# blimpy-1_0-B.net
KiCad netlist of a schematic drawn in EAGLE
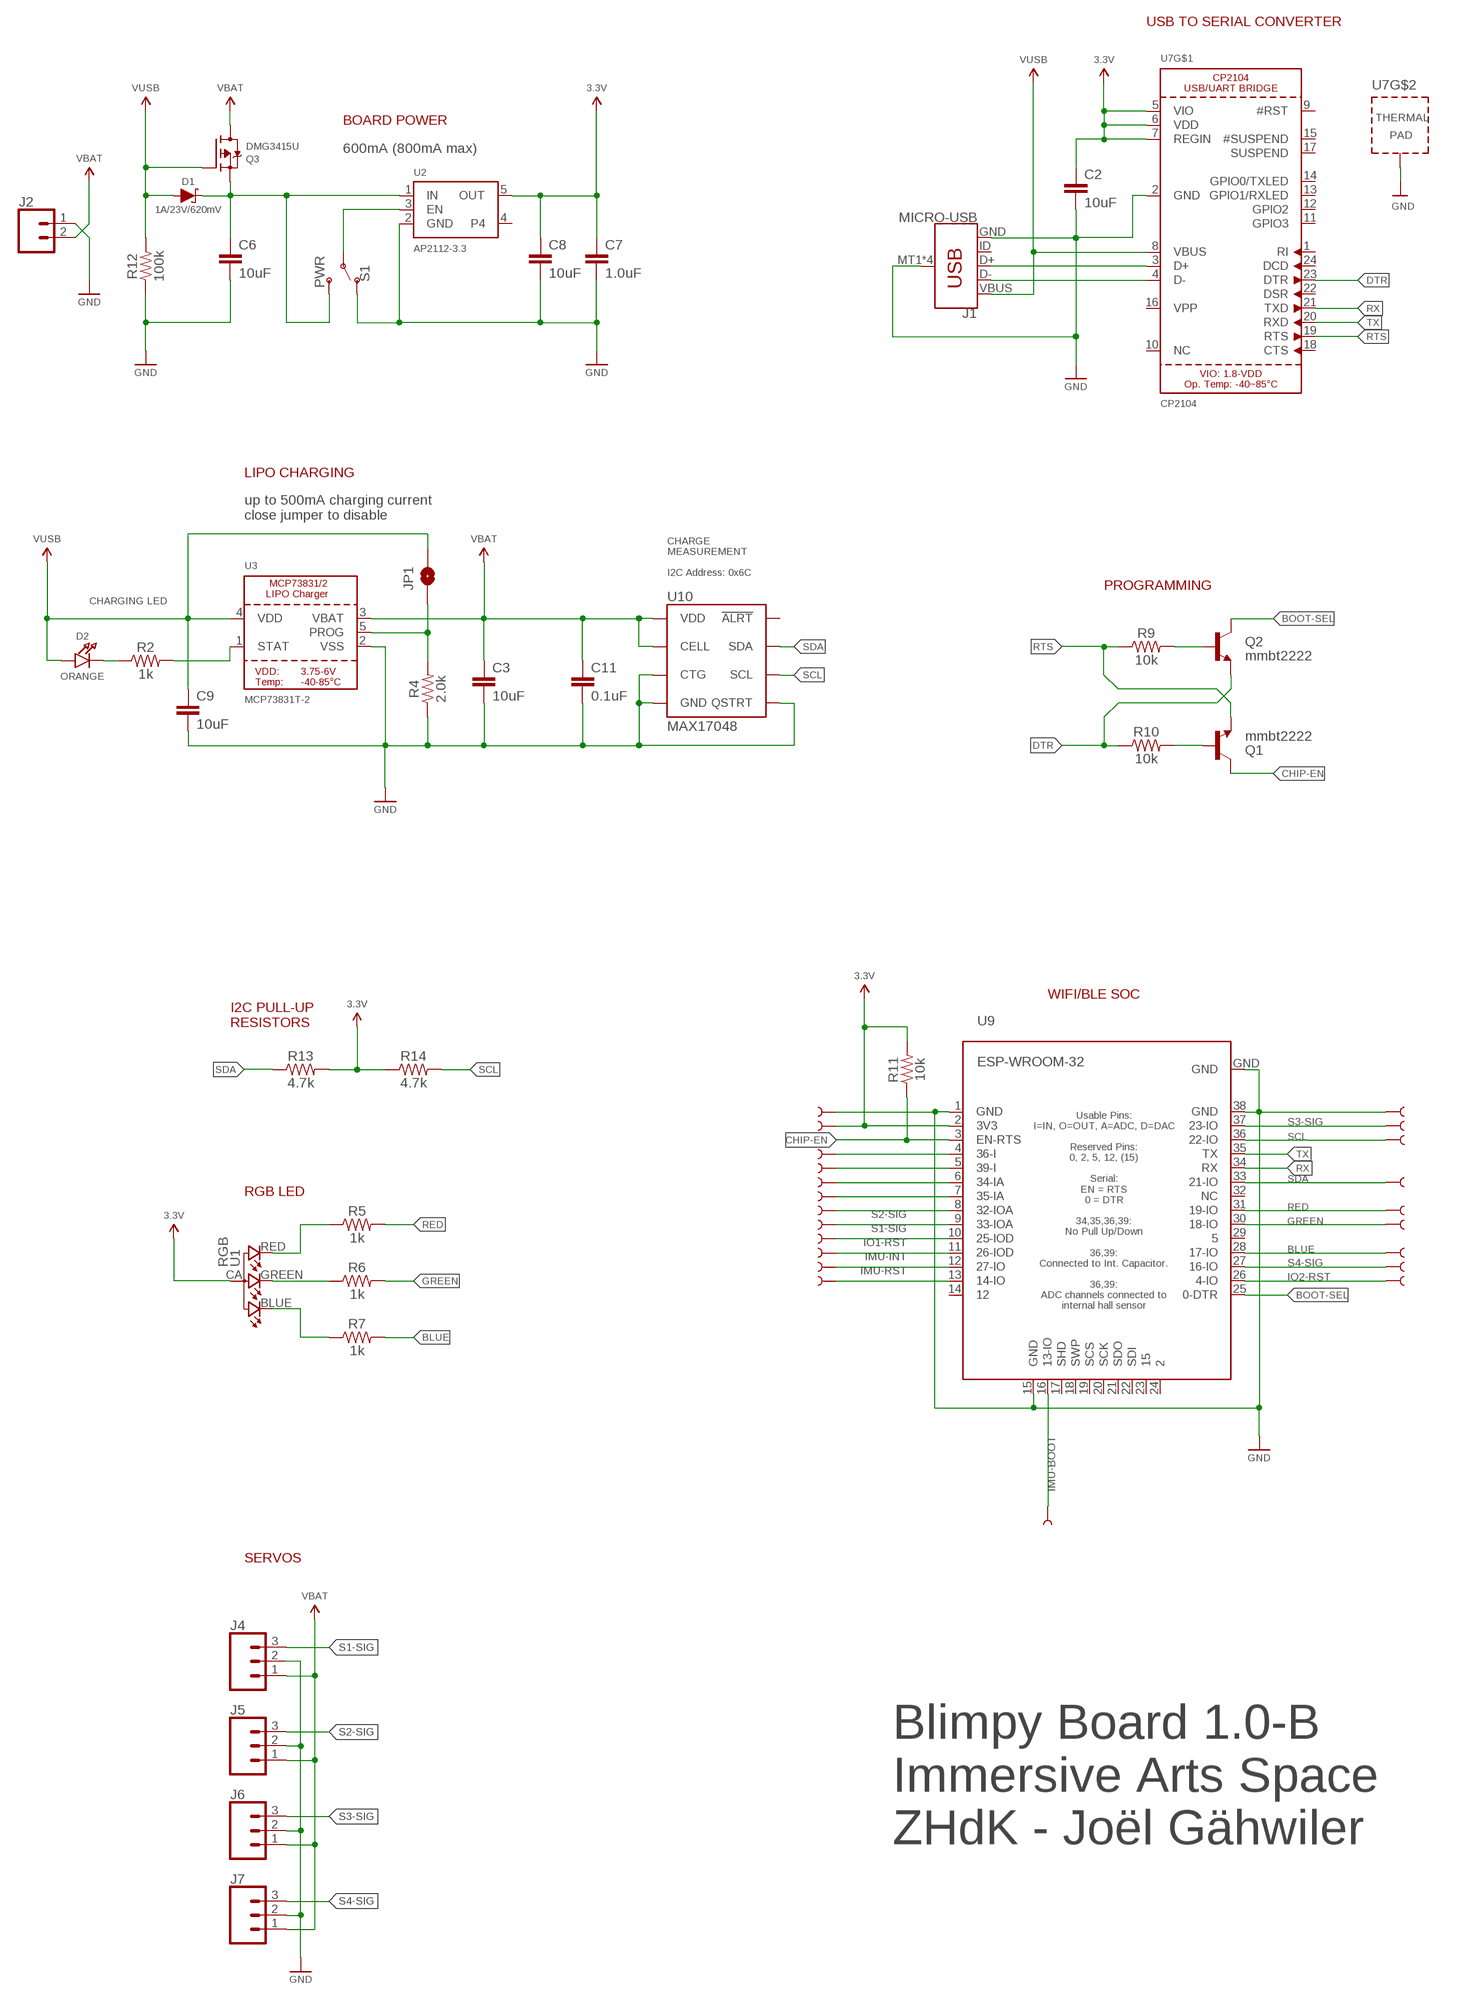
[diagram p0: schematic, sheet 1, part 1 of 2]
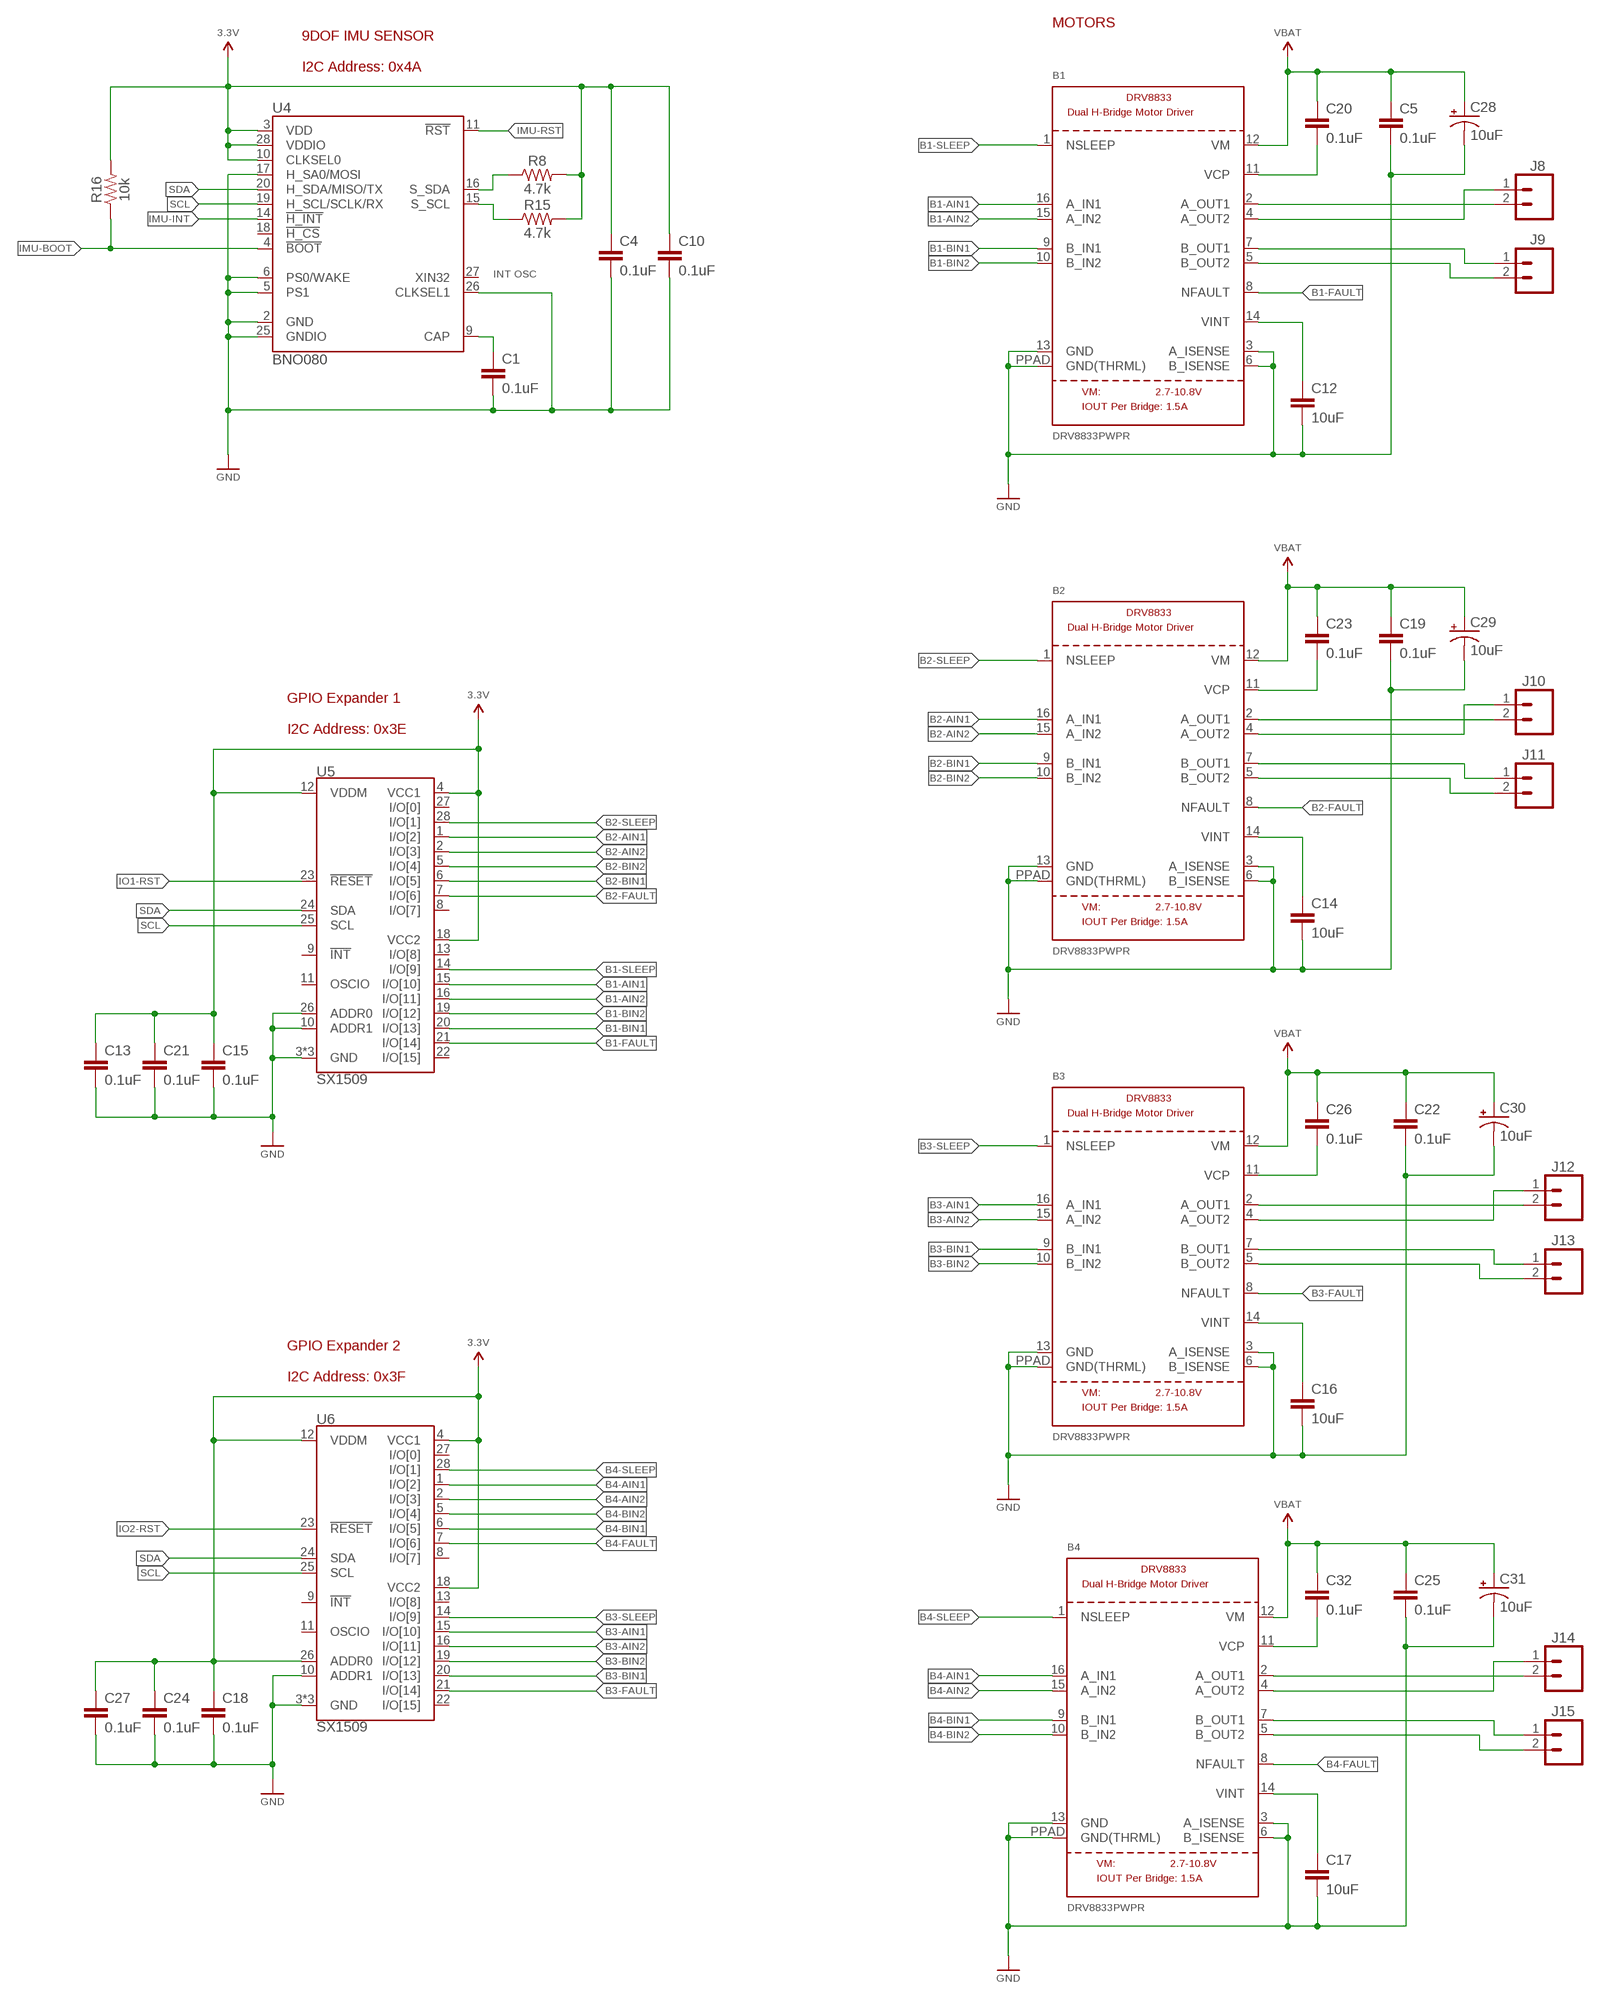
[diagram p1: schematic, sheet 1, part 2 of 2]

(export (version "E")
  (design (tool "Eeschema 10.0.6"))
  (components
    (comp (ref "B1")
      (value "DRV8833PWPR")
      (footprint "eagle-import:HTSSOP16")
      (libsource (lib "eagle-import") (part "DRV8833"))
    )
    (comp (ref "B2")
      (value "DRV8833PWPR")
      (footprint "eagle-import:HTSSOP16")
      (libsource (lib "eagle-import") (part "DRV8833"))
    )
    (comp (ref "B3")
      (value "DRV8833PWPR")
      (footprint "eagle-import:HTSSOP16")
      (libsource (lib "eagle-import") (part "DRV8833"))
    )
    (comp (ref "B4")
      (value "DRV8833PWPR")
      (footprint "eagle-import:HTSSOP16")
      (libsource (lib "eagle-import") (part "DRV8833"))
    )
    (comp (ref "C1")
      (value "0.1uF")
      (footprint "eagle-import:0603")
      (libsource (lib "eagle-import") (part "0.1UF-0603-25V-5%"))
    )
    (comp (ref "C2")
      (value "10uF")
      (footprint "eagle-import:0603")
      (libsource (lib "eagle-import") (part "10UF-0603-6.3V-20%"))
    )
    (comp (ref "C3")
      (value "10uF")
      (footprint "eagle-import:0603")
      (libsource (lib "eagle-import") (part "10UF-0603-6.3V-20%"))
    )
    (comp (ref "C4")
      (value "0.1uF")
      (footprint "eagle-import:0603")
      (libsource (lib "eagle-import") (part "0.1UF-0603-25V-5%"))
    )
    (comp (ref "C5")
      (value "0.1uF")
      (footprint "eagle-import:0603")
      (libsource (lib "eagle-import") (part "0.1UF-0603-25V-5%"))
    )
    (comp (ref "C6")
      (value "10uF")
      (footprint "eagle-import:0603")
      (libsource (lib "eagle-import") (part "10UF-0603-6.3V-20%"))
    )
    (comp (ref "C7")
      (value "1.0uF")
      (footprint "eagle-import:0603")
      (libsource (lib "eagle-import") (part "1.0UF-0603-16V-10%"))
    )
    (comp (ref "C8")
      (value "10uF")
      (footprint "eagle-import:0603")
      (libsource (lib "eagle-import") (part "10UF-0603-6.3V-20%"))
    )
    (comp (ref "C9")
      (value "10uF")
      (footprint "eagle-import:0603")
      (libsource (lib "eagle-import") (part "10UF-0603-6.3V-20%"))
    )
    (comp (ref "C10")
      (value "0.1uF")
      (footprint "eagle-import:0603")
      (libsource (lib "eagle-import") (part "0.1UF-0603-25V-5%"))
    )
    (comp (ref "C11")
      (value "0.1uF")
      (footprint "eagle-import:0603")
      (libsource (lib "eagle-import") (part "SparkFun-Capacitors_510_0.1UF-0603-25V-5%"))
    )
    (comp (ref "C12")
      (value "10uF")
      (footprint "eagle-import:0603")
      (libsource (lib "eagle-import") (part "10UF-0603-6.3V-20%"))
    )
    (comp (ref "C13")
      (value "0.1uF")
      (footprint "eagle-import:0603")
      (libsource (lib "eagle-import") (part "0.1UF-0603-25V-5%"))
    )
    (comp (ref "C14")
      (value "10uF")
      (footprint "eagle-import:0603")
      (libsource (lib "eagle-import") (part "10UF-0603-6.3V-20%"))
    )
    (comp (ref "C15")
      (value "0.1uF")
      (footprint "eagle-import:0603")
      (libsource (lib "eagle-import") (part "SparkFun-Capacitors_510_0.1UF-0603-25V-5%"))
    )
    (comp (ref "C16")
      (value "10uF")
      (footprint "eagle-import:0603")
      (libsource (lib "eagle-import") (part "10UF-0603-6.3V-20%"))
    )
    (comp (ref "C17")
      (value "10uF")
      (footprint "eagle-import:0603")
      (libsource (lib "eagle-import") (part "10UF-0603-6.3V-20%"))
    )
    (comp (ref "C18")
      (value "0.1uF")
      (footprint "eagle-import:0603")
      (libsource (lib "eagle-import") (part "SparkFun-Capacitors_510_0.1UF-0603-25V-5%"))
    )
    (comp (ref "C19")
      (value "0.1uF")
      (footprint "eagle-import:0603")
      (libsource (lib "eagle-import") (part "0.1UF-0603-25V-5%"))
    )
    (comp (ref "C20")
      (value "0.1uF")
      (footprint "eagle-import:0603")
      (libsource (lib "eagle-import") (part "0.1UF-0603-25V-5%"))
    )
    (comp (ref "C21")
      (value "0.1uF")
      (footprint "eagle-import:0603")
      (libsource (lib "eagle-import") (part "0.1UF-0603-25V-5%"))
    )
    (comp (ref "C22")
      (value "0.1uF")
      (footprint "eagle-import:0603")
      (libsource (lib "eagle-import") (part "0.1UF-0603-25V-5%"))
    )
    (comp (ref "C23")
      (value "0.1uF")
      (footprint "eagle-import:0603")
      (libsource (lib "eagle-import") (part "0.1UF-0603-25V-5%"))
    )
    (comp (ref "C24")
      (value "0.1uF")
      (footprint "eagle-import:0603")
      (libsource (lib "eagle-import") (part "0.1UF-0603-25V-5%"))
    )
    (comp (ref "C25")
      (value "0.1uF")
      (footprint "eagle-import:0603")
      (libsource (lib "eagle-import") (part "0.1UF-0603-25V-5%"))
    )
    (comp (ref "C26")
      (value "0.1uF")
      (footprint "eagle-import:0603")
      (libsource (lib "eagle-import") (part "0.1UF-0603-25V-5%"))
    )
    (comp (ref "C27")
      (value "0.1uF")
      (footprint "eagle-import:0603")
      (libsource (lib "eagle-import") (part "0.1UF-0603-25V-5%"))
    )
    (comp (ref "C28")
      (value "10uF")
      (footprint "eagle-import:EIA3216")
      (libsource (lib "eagle-import") (part "10UF-POLAR-EIA3216-16V-10%(TANT)"))
    )
    (comp (ref "C29")
      (value "10uF")
      (footprint "eagle-import:EIA3216")
      (libsource (lib "eagle-import") (part "10UF-POLAR-EIA3216-16V-10%(TANT)"))
    )
    (comp (ref "C30")
      (value "10uF")
      (footprint "eagle-import:EIA3216")
      (libsource (lib "eagle-import") (part "10UF-POLAR-EIA3216-16V-10%(TANT)"))
    )
    (comp (ref "C31")
      (value "10uF")
      (footprint "eagle-import:EIA3216")
      (libsource (lib "eagle-import") (part "10UF-POLAR-EIA3216-16V-10%(TANT)"))
    )
    (comp (ref "C32")
      (value "0.1uF")
      (footprint "eagle-import:0603")
      (libsource (lib "eagle-import") (part "0.1UF-0603-25V-5%"))
    )
    (comp (ref "D1")
      (value "1A/23V/620mV")
      (footprint "eagle-import:SOD-323")
      (libsource (lib "eagle-import") (part "DIODE-SCHOTTKY-BAT20J"))
    )
    (comp (ref "D2")
      (value "ORANGE")
      (footprint "eagle-import:CHIPLED_0805_NOOUTLINE")
      (libsource (lib "eagle-import") (part "LED0805_NOOUTLINE"))
    )
    (comp (ref "J1")
      (value "MICRO-USB")
      (footprint "eagle-import:USB-MICROB")
      (libsource (lib "eagle-import") (part "USB_MICRO-B_SMT"))
    )
    (comp (ref "J2")
      (value "CONN_02-JST-2MM-SMT")
      (footprint "eagle-import:JST-2-SMD")
      (libsource (lib "eagle-import") (part "CONN_02-JST-2MM-SMT"))
    )
    (comp (ref "J4")
      (value "3-PIN SMD")
      (footprint "eagle-import:JST-3-SMD")
      (libsource (lib "eagle-import") (part "CONN_03JST-SMD"))
    )
    (comp (ref "J5")
      (value "3-PIN SMD")
      (footprint "eagle-import:JST-3-SMD")
      (libsource (lib "eagle-import") (part "CONN_03JST-SMD"))
    )
    (comp (ref "J6")
      (value "3-PIN SMD")
      (footprint "eagle-import:JST-3-SMD")
      (libsource (lib "eagle-import") (part "CONN_03JST-SMD"))
    )
    (comp (ref "J7")
      (value "3-PIN SMD")
      (footprint "eagle-import:JST-3-SMD")
      (libsource (lib "eagle-import") (part "CONN_03JST-SMD"))
    )
    (comp (ref "J8")
      (value "CONN_02-JST-2MM-SMT")
      (footprint "eagle-import:JST-2-SMD")
      (libsource (lib "eagle-import") (part "CONN_02-JST-2MM-SMT"))
    )
    (comp (ref "J9")
      (value "CONN_02-JST-2MM-SMT")
      (footprint "eagle-import:JST-2-SMD")
      (libsource (lib "eagle-import") (part "CONN_02-JST-2MM-SMT"))
    )
    (comp (ref "J10")
      (value "CONN_02-JST-2MM-SMT")
      (footprint "eagle-import:JST-2-SMD")
      (libsource (lib "eagle-import") (part "CONN_02-JST-2MM-SMT"))
    )
    (comp (ref "J11")
      (value "CONN_02-JST-2MM-SMT")
      (footprint "eagle-import:JST-2-SMD")
      (libsource (lib "eagle-import") (part "CONN_02-JST-2MM-SMT"))
    )
    (comp (ref "J12")
      (value "CONN_02-JST-2MM-SMT")
      (footprint "eagle-import:JST-2-SMD")
      (libsource (lib "eagle-import") (part "CONN_02-JST-2MM-SMT"))
    )
    (comp (ref "J13")
      (value "CONN_02-JST-2MM-SMT")
      (footprint "eagle-import:JST-2-SMD")
      (libsource (lib "eagle-import") (part "CONN_02-JST-2MM-SMT"))
    )
    (comp (ref "J14")
      (value "CONN_02-JST-2MM-SMT")
      (footprint "eagle-import:JST-2-SMD")
      (libsource (lib "eagle-import") (part "CONN_02-JST-2MM-SMT"))
    )
    (comp (ref "J15")
      (value "CONN_02-JST-2MM-SMT")
      (footprint "eagle-import:JST-2-SMD")
      (libsource (lib "eagle-import") (part "CONN_02-JST-2MM-SMT"))
    )
    (comp (ref "JP1")
      (value "JUMPER-SMT_2_NO_SILK")
      (footprint "eagle-import:SMT-JUMPER_2_NO_SILK")
      (libsource (lib "eagle-import") (part "JUMPER-SMT_2_NO_SILK"))
    )
    (comp (ref "Q1")
      (value "mmbt2222")
      (footprint "eagle-import:SOT23-3")
      (libsource (lib "eagle-import") (part "TRANSISTOR_NPNSOT23-3"))
    )
    (comp (ref "Q2")
      (value "mmbt2222")
      (footprint "eagle-import:SOT23-3")
      (libsource (lib "eagle-import") (part "TRANSISTOR_NPNSOT23-3"))
    )
    (comp (ref "Q3")
      (value "DMG3415U")
      (footprint "eagle-import:SOT23-R")
      (libsource (lib "eagle-import") (part "MOSFET-P"))
    )
    (comp (ref "R2")
      (value "1k")
      (footprint "eagle-import:0603")
      (libsource (lib "eagle-import") (part "1KOHM-0603-1/10W-1%"))
    )
    (comp (ref "R4")
      (value "2.0k")
      (footprint "eagle-import:0603")
      (libsource (lib "eagle-import") (part "2.0KOHM-0603-1/10W-5%"))
    )
    (comp (ref "R5")
      (value "1k")
      (footprint "eagle-import:0603")
      (libsource (lib "eagle-import") (part "1KOHM-0603-1/10W-1%"))
    )
    (comp (ref "R6")
      (value "1k")
      (footprint "eagle-import:0603")
      (libsource (lib "eagle-import") (part "1KOHM-0603-1/10W-1%"))
    )
    (comp (ref "R7")
      (value "1k")
      (footprint "eagle-import:0603")
      (libsource (lib "eagle-import") (part "1KOHM-0603-1/10W-1%"))
    )
    (comp (ref "R8")
      (value "4.7k")
      (footprint "eagle-import:0603")
      (libsource (lib "eagle-import") (part "4.7KOHM-0603-1/10W-1%"))
    )
    (comp (ref "R9")
      (value "10k")
      (footprint "eagle-import:0603")
      (libsource (lib "eagle-import") (part "10KOHM-0603-1/10W-1%"))
    )
    (comp (ref "R10")
      (value "10k")
      (footprint "eagle-import:0603")
      (libsource (lib "eagle-import") (part "10KOHM-0603-1/10W-1%"))
    )
    (comp (ref "R11")
      (value "10k")
      (footprint "eagle-import:0603")
      (libsource (lib "eagle-import") (part "10KOHM-0603-1/10W-1%"))
    )
    (comp (ref "R12")
      (value "100k")
      (footprint "eagle-import:0603")
      (libsource (lib "eagle-import") (part "100KOHM-0603-1/10W-1%"))
    )
    (comp (ref "R13")
      (value "4.7k")
      (footprint "eagle-import:0603")
      (libsource (lib "eagle-import") (part "4.7KOHM-0603-1/10W-1%"))
    )
    (comp (ref "R14")
      (value "4.7k")
      (footprint "eagle-import:0603")
      (libsource (lib "eagle-import") (part "4.7KOHM-0603-1/10W-1%"))
    )
    (comp (ref "R15")
      (value "4.7k")
      (footprint "eagle-import:0603")
      (libsource (lib "eagle-import") (part "4.7KOHM-0603-1/10W-1%"))
    )
    (comp (ref "R16")
      (value "10k")
      (footprint "eagle-import:0603")
      (libsource (lib "eagle-import") (part "10KOHM-0603-1/10W-1%"))
    )
    (comp (ref "S1")
      (value "PWR")
      (footprint "eagle-import:SWITCH_SPST_SMD_A")
      (libsource (lib "eagle-import") (part "SWITCH-SPDT-SMD-RIGHT-ANGLE"))
    )
    (comp (ref "TP1")
      (value "TEST-POINT3")
      (footprint "eagle-import:PAD.03X.03")
      (libsource (lib "eagle-import") (part "TEST-POINT3"))
    )
    (comp (ref "TP2")
      (value "TEST-POINT3")
      (footprint "eagle-import:PAD.03X.03")
      (libsource (lib "eagle-import") (part "TEST-POINT3"))
    )
    (comp (ref "TP3")
      (value "TEST-POINT3")
      (footprint "eagle-import:PAD.03X.03")
      (libsource (lib "eagle-import") (part "TEST-POINT3"))
    )
    (comp (ref "TP4")
      (value "TEST-POINT3")
      (footprint "eagle-import:PAD.03X.03")
      (libsource (lib "eagle-import") (part "TEST-POINT3"))
    )
    (comp (ref "TP5")
      (value "TEST-POINT3")
      (footprint "eagle-import:PAD.03X.03")
      (libsource (lib "eagle-import") (part "TEST-POINT3"))
    )
    (comp (ref "TP6")
      (value "TEST-POINT3")
      (footprint "eagle-import:PAD.03X.03")
      (libsource (lib "eagle-import") (part "TEST-POINT3"))
    )
    (comp (ref "TP7")
      (value "TEST-POINT3")
      (footprint "eagle-import:PAD.03X.03")
      (libsource (lib "eagle-import") (part "TEST-POINT3"))
    )
    (comp (ref "TP8")
      (value "TEST-POINT3")
      (footprint "eagle-import:PAD.03X.03")
      (libsource (lib "eagle-import") (part "TEST-POINT3"))
    )
    (comp (ref "TP9")
      (value "TEST-POINT3")
      (footprint "eagle-import:PAD.03X.03")
      (libsource (lib "eagle-import") (part "TEST-POINT3"))
    )
    (comp (ref "TP10")
      (value "TEST-POINT3")
      (footprint "eagle-import:PAD.03X.03")
      (libsource (lib "eagle-import") (part "TEST-POINT3"))
    )
    (comp (ref "TP11")
      (value "TEST-POINT3")
      (footprint "eagle-import:PAD.03X.03")
      (libsource (lib "eagle-import") (part "TEST-POINT3"))
    )
    (comp (ref "TP12")
      (value "TEST-POINT3")
      (footprint "eagle-import:PAD.03X.03")
      (libsource (lib "eagle-import") (part "TEST-POINT3"))
    )
    (comp (ref "TP13")
      (value "TEST-POINT3")
      (footprint "eagle-import:PAD.03X.03")
      (libsource (lib "eagle-import") (part "TEST-POINT3"))
    )
    (comp (ref "TP14")
      (value "TEST-POINT3")
      (footprint "eagle-import:PAD.03X.03")
      (libsource (lib "eagle-import") (part "TEST-POINT3"))
    )
    (comp (ref "TP15")
      (value "TEST-POINT3")
      (footprint "eagle-import:PAD.03X.03")
      (libsource (lib "eagle-import") (part "TEST-POINT3"))
    )
    (comp (ref "TP16")
      (value "TEST-POINT3")
      (footprint "eagle-import:PAD.03X.03")
      (libsource (lib "eagle-import") (part "TEST-POINT3"))
    )
    (comp (ref "TP17")
      (value "TEST-POINT3")
      (footprint "eagle-import:PAD.03X.03")
      (libsource (lib "eagle-import") (part "TEST-POINT3"))
    )
    (comp (ref "TP18")
      (value "TEST-POINT3")
      (footprint "eagle-import:PAD.03X.03")
      (libsource (lib "eagle-import") (part "TEST-POINT3"))
    )
    (comp (ref "TP19")
      (value "TEST-POINT3")
      (footprint "eagle-import:PAD.03X.03")
      (libsource (lib "eagle-import") (part "TEST-POINT3"))
    )
    (comp (ref "TP20")
      (value "TEST-POINT3")
      (footprint "eagle-import:PAD.03X.03")
      (libsource (lib "eagle-import") (part "TEST-POINT3"))
    )
    (comp (ref "TP21")
      (value "TEST-POINT3")
      (footprint "eagle-import:PAD.03X.03")
      (libsource (lib "eagle-import") (part "TEST-POINT3"))
    )
    (comp (ref "TP22")
      (value "TEST-POINT3")
      (footprint "eagle-import:PAD.03X.03")
      (libsource (lib "eagle-import") (part "TEST-POINT3"))
    )
    (comp (ref "U1")
      (value "RGB")
      (footprint "eagle-import:PLCC4-2MM-RGB")
      (libsource (lib "eagle-import") (part "RGB-LED-CLMVB-FKARGB"))
    )
    (comp (ref "U2")
      (value "AP2112-3.3")
      (footprint "eagle-import:SOT23-5")
      (libsource (lib "eagle-import") (part "VREG_SOT23-5"))
    )
    (comp (ref "U3")
      (value "MCP73831T-2")
      (footprint "eagle-import:SOT23-5")
      (libsource (lib "eagle-import") (part "MCP73831/2"))
    )
    (comp (ref "U4")
      (value "BNO080")
      (footprint "eagle-import:LGA-28")
      (libsource (lib "eagle-import") (part "BNO080"))
    )
    (comp (ref "U5")
      (value "SX1509")
      (footprint "eagle-import:QFN-28")
      (libsource (lib "eagle-import") (part "SX1509"))
    )
    (comp (ref "U6")
      (value "SX1509")
      (footprint "eagle-import:QFN-28")
      (libsource (lib "eagle-import") (part "SX1509"))
    )
    (comp (ref "U7")
      (value "CP2104")
      (footprint "eagle-import:QFN24_4MM_SMSC")
      (libsource (lib "eagle-import") (part "CP2104"))
    )
    (comp (ref "U9")
      (value "ESP-WROOM-32")
      (footprint "eagle-import:ESP-WROOM-32")
      (libsource (lib "eagle-import") (part "ESP-WROOM-32"))
    )
    (comp (ref "U10")
      (value "MAX17048")
      (footprint "eagle-import:DFN-8")
      (libsource (lib "eagle-import") (part "MAX17048DFN8"))
    )
  )
  (nets
    (net (code "1") (name "3.3V") (class "Default")
      (node (ref "C10") (pin "1") (pinfunction "1_1") (pintype "passive"))
      (node (ref "C13") (pin "1") (pinfunction "1_1") (pintype "passive"))
      (node (ref "C15") (pin "1") (pinfunction "1_1") (pintype "passive"))
      (node (ref "C18") (pin "1") (pinfunction "1_1") (pintype "passive"))
      (node (ref "C2") (pin "1") (pinfunction "1_1") (pintype "passive"))
      (node (ref "C21") (pin "1") (pinfunction "1_1") (pintype "passive"))
      (node (ref "C24") (pin "1") (pinfunction "1_1") (pintype "passive"))
      (node (ref "C27") (pin "1") (pinfunction "1_1") (pintype "passive"))
      (node (ref "C4") (pin "1") (pinfunction "1_1") (pintype "passive"))
      (node (ref "C7") (pin "1") (pinfunction "1_1") (pintype "passive"))
      (node (ref "C8") (pin "1") (pinfunction "1_1") (pintype "passive"))
      (node (ref "R11") (pin "2") (pinfunction "2_2") (pintype "passive"))
      (node (ref "R13") (pin "2") (pinfunction "2_2") (pintype "passive"))
      (node (ref "R14") (pin "1") (pinfunction "1_1") (pintype "passive"))
      (node (ref "R15") (pin "2") (pinfunction "2_2") (pintype "passive"))
      (node (ref "R16") (pin "2") (pinfunction "2_2") (pintype "passive"))
      (node (ref "R8") (pin "2") (pinfunction "2_2") (pintype "passive"))
      (node (ref "TP11") (pin "P$1") (pinfunction "1_P$1") (pintype "bidirectional"))
      (node (ref "U1") (pin "CA") (pinfunction "1_CA") (pintype "passive"))
      (node (ref "U2") (pin "5") (pinfunction "OUT_5") (pintype "power_in"))
      (node (ref "U4") (pin "10") (pinfunction "CLKSEL0_10") (pintype "bidirectional"))
      (node (ref "U4") (pin "28") (pinfunction "VDDIO_28") (pintype "bidirectional"))
      (node (ref "U4") (pin "3") (pinfunction "VDD_3") (pintype "bidirectional"))
      (node (ref "U5") (pin "12") (pinfunction "VDDM_12") (pintype "bidirectional"))
      (node (ref "U5") (pin "18") (pinfunction "VCC2_18") (pintype "bidirectional"))
      (node (ref "U5") (pin "4") (pinfunction "VCC1_4") (pintype "bidirectional"))
      (node (ref "U6") (pin "12") (pinfunction "VDDM_12") (pintype "bidirectional"))
      (node (ref "U6") (pin "18") (pinfunction "VCC2_18") (pintype "bidirectional"))
      (node (ref "U6") (pin "26") (pinfunction "ADDR0_26") (pintype "bidirectional"))
      (node (ref "U6") (pin "4") (pinfunction "VCC1_4") (pintype "bidirectional"))
      (node (ref "U7") (pin "5") (pinfunction "VIO_5") (pintype "power_in"))
      (node (ref "U7") (pin "6") (pinfunction "VDD_6") (pintype "power_in"))
      (node (ref "U7") (pin "7") (pinfunction "REGIN_7") (pintype "power_in"))
      (node (ref "U9") (pin "2") (pinfunction "3V3_2") (pintype "bidirectional"))
    )
    (net (code "2") (name "B1-AIN1") (class "Default")
      (node (ref "B1") (pin "16") (pinfunction "A_IN1_16") (pintype "input"))
      (node (ref "U5") (pin "15") (pinfunction "I/O[10]_15") (pintype "bidirectional"))
    )
    (net (code "3") (name "B1-AIN2") (class "Default")
      (node (ref "B1") (pin "15") (pinfunction "A_IN2_15") (pintype "input"))
      (node (ref "U5") (pin "16") (pinfunction "I/O[11]_16") (pintype "bidirectional"))
    )
    (net (code "4") (name "B1-BIN1") (class "Default")
      (node (ref "B1") (pin "9") (pinfunction "B_IN1_9") (pintype "input"))
      (node (ref "U5") (pin "20") (pinfunction "I/O[13]_20") (pintype "bidirectional"))
    )
    (net (code "5") (name "B1-BIN2") (class "Default")
      (node (ref "B1") (pin "10") (pinfunction "B_IN2_10") (pintype "input"))
      (node (ref "U5") (pin "19") (pinfunction "I/O[12]_19") (pintype "bidirectional"))
    )
    (net (code "6") (name "B1-FAULT") (class "Default")
      (node (ref "B1") (pin "8") (pinfunction "NFAULT_8") (pintype "bidirectional"))
      (node (ref "U5") (pin "21") (pinfunction "I/O[14]_21") (pintype "bidirectional"))
    )
    (net (code "7") (name "B1-SLEEP") (class "Default")
      (node (ref "B1") (pin "1") (pinfunction "NSLEEP_1") (pintype "input"))
      (node (ref "U5") (pin "14") (pinfunction "I/O[9]_14") (pintype "bidirectional"))
    )
    (net (code "8") (name "B2-AIN1") (class "Default")
      (node (ref "B2") (pin "16") (pinfunction "A_IN1_16") (pintype "input"))
      (node (ref "U5") (pin "1") (pinfunction "I/O[2]_1") (pintype "bidirectional"))
    )
    (net (code "9") (name "B2-AIN2") (class "Default")
      (node (ref "B2") (pin "15") (pinfunction "A_IN2_15") (pintype "input"))
      (node (ref "U5") (pin "2") (pinfunction "I/O[3]_2") (pintype "bidirectional"))
    )
    (net (code "10") (name "B2-BIN1") (class "Default")
      (node (ref "B2") (pin "9") (pinfunction "B_IN1_9") (pintype "input"))
      (node (ref "U5") (pin "6") (pinfunction "I/O[5]_6") (pintype "bidirectional"))
    )
    (net (code "11") (name "B2-BIN2") (class "Default")
      (node (ref "B2") (pin "10") (pinfunction "B_IN2_10") (pintype "input"))
      (node (ref "U5") (pin "5") (pinfunction "I/O[4]_5") (pintype "bidirectional"))
    )
    (net (code "12") (name "B2-FAULT") (class "Default")
      (node (ref "B2") (pin "8") (pinfunction "NFAULT_8") (pintype "bidirectional"))
      (node (ref "U5") (pin "7") (pinfunction "I/O[6]_7") (pintype "bidirectional"))
    )
    (net (code "13") (name "B2-SLEEP") (class "Default")
      (node (ref "B2") (pin "1") (pinfunction "NSLEEP_1") (pintype "input"))
      (node (ref "U5") (pin "28") (pinfunction "I/O[1]_28") (pintype "bidirectional"))
    )
    (net (code "14") (name "B3-AIN1") (class "Default")
      (node (ref "B3") (pin "16") (pinfunction "A_IN1_16") (pintype "input"))
      (node (ref "U6") (pin "15") (pinfunction "I/O[10]_15") (pintype "bidirectional"))
    )
    (net (code "15") (name "B3-AIN2") (class "Default")
      (node (ref "B3") (pin "15") (pinfunction "A_IN2_15") (pintype "input"))
      (node (ref "U6") (pin "16") (pinfunction "I/O[11]_16") (pintype "bidirectional"))
    )
    (net (code "16") (name "B3-BIN1") (class "Default")
      (node (ref "B3") (pin "9") (pinfunction "B_IN1_9") (pintype "input"))
      (node (ref "U6") (pin "20") (pinfunction "I/O[13]_20") (pintype "bidirectional"))
    )
    (net (code "17") (name "B3-BIN2") (class "Default")
      (node (ref "B3") (pin "10") (pinfunction "B_IN2_10") (pintype "input"))
      (node (ref "U6") (pin "19") (pinfunction "I/O[12]_19") (pintype "bidirectional"))
    )
    (net (code "18") (name "B3-FAULT") (class "Default")
      (node (ref "B3") (pin "8") (pinfunction "NFAULT_8") (pintype "bidirectional"))
      (node (ref "U6") (pin "21") (pinfunction "I/O[14]_21") (pintype "bidirectional"))
    )
    (net (code "19") (name "B3-SLEEP") (class "Default")
      (node (ref "B3") (pin "1") (pinfunction "NSLEEP_1") (pintype "input"))
      (node (ref "U6") (pin "14") (pinfunction "I/O[9]_14") (pintype "bidirectional"))
    )
    (net (code "20") (name "B4-AIN1") (class "Default")
      (node (ref "B4") (pin "16") (pinfunction "A_IN1_16") (pintype "input"))
      (node (ref "U6") (pin "1") (pinfunction "I/O[2]_1") (pintype "bidirectional"))
    )
    (net (code "21") (name "B4-AIN2") (class "Default")
      (node (ref "B4") (pin "15") (pinfunction "A_IN2_15") (pintype "input"))
      (node (ref "U6") (pin "2") (pinfunction "I/O[3]_2") (pintype "bidirectional"))
    )
    (net (code "22") (name "B4-BIN1") (class "Default")
      (node (ref "B4") (pin "9") (pinfunction "B_IN1_9") (pintype "input"))
      (node (ref "U6") (pin "6") (pinfunction "I/O[5]_6") (pintype "bidirectional"))
    )
    (net (code "23") (name "B4-BIN2") (class "Default")
      (node (ref "B4") (pin "10") (pinfunction "B_IN2_10") (pintype "input"))
      (node (ref "U6") (pin "5") (pinfunction "I/O[4]_5") (pintype "bidirectional"))
    )
    (net (code "24") (name "B4-FAULT") (class "Default")
      (node (ref "B4") (pin "8") (pinfunction "NFAULT_8") (pintype "bidirectional"))
      (node (ref "U6") (pin "7") (pinfunction "I/O[6]_7") (pintype "bidirectional"))
    )
    (net (code "25") (name "B4-SLEEP") (class "Default")
      (node (ref "B4") (pin "1") (pinfunction "NSLEEP_1") (pintype "input"))
      (node (ref "U6") (pin "28") (pinfunction "I/O[1]_28") (pintype "bidirectional"))
    )
    (net (code "26") (name "BLUE") (class "Default")
      (node (ref "R7") (pin "2") (pinfunction "2_2") (pintype "passive"))
      (node (ref "TP22") (pin "P$1") (pinfunction "1_P$1") (pintype "bidirectional"))
      (node (ref "U9") (pin "28") (pinfunction "17-IO_28") (pintype "bidirectional"))
    )
    (net (code "27") (name "BOOT-SEL") (class "Default")
      (node (ref "Q2") (pin "3") (pinfunction "C_3") (pintype "passive"))
      (node (ref "U9") (pin "25") (pinfunction "0-DTR_25") (pintype "bidirectional"))
    )
    (net (code "28") (name "CHIP-EN") (class "Default")
      (node (ref "Q1") (pin "3") (pinfunction "C_3") (pintype "passive"))
      (node (ref "R11") (pin "1") (pinfunction "1_1") (pintype "passive"))
      (node (ref "U9") (pin "3") (pinfunction "EN-RTS_3") (pintype "bidirectional"))
    )
    (net (code "29") (name "DTR") (class "Default")
      (node (ref "Q2") (pin "2") (pinfunction "E_2") (pintype "passive"))
      (node (ref "R10") (pin "1") (pinfunction "1_1") (pintype "passive"))
      (node (ref "U7") (pin "23") (pinfunction "DTR_23") (pintype "output"))
    )
    (net (code "30") (name "GND") (class "Default")
      (node (ref "B1") (pin "13") (pinfunction "GND_13") (pintype "power_in"))
      (node (ref "B1") (pin "3") (pinfunction "A_ISENSE_3") (pintype "bidirectional"))
      (node (ref "B1") (pin "6") (pinfunction "B_ISENSE_6") (pintype "bidirectional"))
      (node (ref "B1") (pin "PPAD") (pinfunction "GND(THRML)_PPAD") (pintype "power_in"))
      (node (ref "B2") (pin "13") (pinfunction "GND_13") (pintype "power_in"))
      (node (ref "B2") (pin "3") (pinfunction "A_ISENSE_3") (pintype "bidirectional"))
      (node (ref "B2") (pin "6") (pinfunction "B_ISENSE_6") (pintype "bidirectional"))
      (node (ref "B2") (pin "PPAD") (pinfunction "GND(THRML)_PPAD") (pintype "power_in"))
      (node (ref "B3") (pin "13") (pinfunction "GND_13") (pintype "power_in"))
      (node (ref "B3") (pin "3") (pinfunction "A_ISENSE_3") (pintype "bidirectional"))
      (node (ref "B3") (pin "6") (pinfunction "B_ISENSE_6") (pintype "bidirectional"))
      (node (ref "B3") (pin "PPAD") (pinfunction "GND(THRML)_PPAD") (pintype "power_in"))
      (node (ref "B4") (pin "13") (pinfunction "GND_13") (pintype "power_in"))
      (node (ref "B4") (pin "3") (pinfunction "A_ISENSE_3") (pintype "bidirectional"))
      (node (ref "B4") (pin "6") (pinfunction "B_ISENSE_6") (pintype "bidirectional"))
      (node (ref "B4") (pin "PPAD") (pinfunction "GND(THRML)_PPAD") (pintype "power_in"))
      (node (ref "C1") (pin "2") (pinfunction "2_2") (pintype "passive"))
      (node (ref "C10") (pin "2") (pinfunction "2_2") (pintype "passive"))
      (node (ref "C11") (pin "2") (pinfunction "2_2") (pintype "passive"))
      (node (ref "C12") (pin "2") (pinfunction "2_2") (pintype "passive"))
      (node (ref "C13") (pin "2") (pinfunction "2_2") (pintype "passive"))
      (node (ref "C14") (pin "2") (pinfunction "2_2") (pintype "passive"))
      (node (ref "C15") (pin "2") (pinfunction "2_2") (pintype "passive"))
      (node (ref "C16") (pin "2") (pinfunction "2_2") (pintype "passive"))
      (node (ref "C17") (pin "2") (pinfunction "2_2") (pintype "passive"))
      (node (ref "C18") (pin "2") (pinfunction "2_2") (pintype "passive"))
      (node (ref "C19") (pin "2") (pinfunction "2_2") (pintype "passive"))
      (node (ref "C2") (pin "2") (pinfunction "2_2") (pintype "passive"))
      (node (ref "C21") (pin "2") (pinfunction "2_2") (pintype "passive"))
      (node (ref "C22") (pin "2") (pinfunction "2_2") (pintype "passive"))
      (node (ref "C24") (pin "2") (pinfunction "2_2") (pintype "passive"))
      (node (ref "C25") (pin "2") (pinfunction "2_2") (pintype "passive"))
      (node (ref "C27") (pin "2") (pinfunction "2_2") (pintype "passive"))
      (node (ref "C28") (pin "-") (pinfunction "-_-") (pintype "passive"))
      (node (ref "C29") (pin "-") (pinfunction "-_-") (pintype "passive"))
      (node (ref "C3") (pin "2") (pinfunction "2_2") (pintype "passive"))
      (node (ref "C30") (pin "-") (pinfunction "-_-") (pintype "passive"))
      (node (ref "C31") (pin "-") (pinfunction "-_-") (pintype "passive"))
      (node (ref "C4") (pin "2") (pinfunction "2_2") (pintype "passive"))
      (node (ref "C5") (pin "2") (pinfunction "2_2") (pintype "passive"))
      (node (ref "C6") (pin "2") (pinfunction "2_2") (pintype "passive"))
      (node (ref "C7") (pin "2") (pinfunction "2_2") (pintype "passive"))
      (node (ref "C8") (pin "2") (pinfunction "2_2") (pintype "passive"))
      (node (ref "C9") (pin "2") (pinfunction "2_2") (pintype "passive"))
      (node (ref "J1") (pin "GND") (pinfunction "GND_GND") (pintype "power_in"))
      (node (ref "J1") (pin "MT1") (pinfunction "SHIELD_MT1") (pintype "bidirectional"))
      (node (ref "J1") (pin "MT2") (pinfunction "SHIELD_MT2") (pintype "bidirectional"))
      (node (ref "J1") (pin "P$1") (pinfunction "SHIELD_P$1") (pintype "bidirectional"))
      (node (ref "J1") (pin "P$2") (pinfunction "SHIELD_P$2") (pintype "bidirectional"))
      (node (ref "J2") (pin "1") (pinfunction "2_1") (pintype "passive"))
      (node (ref "J4") (pin "2") (pinfunction "2_2") (pintype "passive"))
      (node (ref "J5") (pin "2") (pinfunction "2_2") (pintype "passive"))
      (node (ref "J6") (pin "2") (pinfunction "2_2") (pintype "passive"))
      (node (ref "J7") (pin "2") (pinfunction "2_2") (pintype "passive"))
      (node (ref "R12") (pin "1") (pinfunction "1_1") (pintype "passive"))
      (node (ref "R4") (pin "1") (pinfunction "1_1") (pintype "passive"))
      (node (ref "S1") (pin "1") (pinfunction "O_1") (pintype "passive"))
      (node (ref "TP12") (pin "P$1") (pinfunction "1_P$1") (pintype "bidirectional"))
      (node (ref "TP13") (pin "P$1") (pinfunction "1_P$1") (pintype "bidirectional"))
      (node (ref "U10") (pin "P$1") (pinfunction "CTG_P$1") (pintype "input"))
      (node (ref "U10") (pin "P$4") (pinfunction "GND_P$4") (pintype "bidirectional"))
      (node (ref "U10") (pin "P$6") (pinfunction "QSTRT_P$6") (pintype "bidirectional"))
      (node (ref "U10") (pin "P$9") (pinfunction "GND_P$9") (pintype "bidirectional"))
      (node (ref "U2") (pin "2") (pinfunction "GND_2") (pintype "power_in"))
      (node (ref "U3") (pin "2") (pinfunction "VSS_2") (pintype "power_in"))
      (node (ref "U4") (pin "17") (pinfunction "H_SA0/MOSI_17") (pintype "bidirectional"))
      (node (ref "U4") (pin "2") (pinfunction "GND_2") (pintype "bidirectional"))
      (node (ref "U4") (pin "25") (pinfunction "GNDIO_25") (pintype "bidirectional"))
      (node (ref "U4") (pin "26") (pinfunction "CLKSEL1_26") (pintype "bidirectional"))
      (node (ref "U4") (pin "5") (pinfunction "PS1_5") (pintype "bidirectional"))
      (node (ref "U4") (pin "6") (pinfunction "PS0/WAKE_6") (pintype "bidirectional"))
      (node (ref "U5") (pin "10") (pinfunction "ADDR1_10") (pintype "bidirectional"))
      (node (ref "U5") (pin "17") (pinfunction "GND_17") (pintype "bidirectional"))
      (node (ref "U5") (pin "26") (pinfunction "ADDR0_26") (pintype "bidirectional"))
      (node (ref "U5") (pin "29") (pinfunction "GND_29") (pintype "bidirectional"))
      (node (ref "U5") (pin "3") (pinfunction "GND_3") (pintype "bidirectional"))
      (node (ref "U6") (pin "10") (pinfunction "ADDR1_10") (pintype "bidirectional"))
      (node (ref "U6") (pin "17") (pinfunction "GND_17") (pintype "bidirectional"))
      (node (ref "U6") (pin "29") (pinfunction "GND_29") (pintype "bidirectional"))
      (node (ref "U6") (pin "3") (pinfunction "GND_3") (pintype "bidirectional"))
      (node (ref "U7") (pin "2") (pinfunction "GND_2") (pintype "power_in"))
      (node (ref "U7") (pin "THERM") (pinfunction "TP_THERM") (pintype "power_in"))
      (node (ref "U9") (pin "1") (pinfunction "GND_1") (pintype "bidirectional"))
      (node (ref "U9") (pin "15") (pinfunction "GND_15") (pintype "bidirectional"))
      (node (ref "U9") (pin "38") (pinfunction "GND_38") (pintype "bidirectional"))
      (node (ref "U9") (pin "GND") (pinfunction "GND_GND") (pintype "bidirectional"))
    )
    (net (code "31") (name "GREEN") (class "Default")
      (node (ref "R6") (pin "2") (pinfunction "2_2") (pintype "passive"))
      (node (ref "TP21") (pin "P$1") (pinfunction "1_P$1") (pintype "bidirectional"))
      (node (ref "U9") (pin "30") (pinfunction "18-IO_30") (pintype "bidirectional"))
    )
    (net (code "32") (name "IMU-BOOT") (class "Default")
      (node (ref "R16") (pin "1") (pinfunction "1_1") (pintype "passive"))
      (node (ref "TP17") (pin "P$1") (pinfunction "1_P$1") (pintype "bidirectional"))
      (node (ref "U4") (pin "4") (pinfunction "~{BOOT}_4") (pintype "bidirectional"))
      (node (ref "U9") (pin "16") (pinfunction "13-IO_16") (pintype "bidirectional"))
    )
    (net (code "33") (name "IMU-INT") (class "Default")
      (node (ref "TP4") (pin "P$1") (pinfunction "1_P$1") (pintype "bidirectional"))
      (node (ref "U4") (pin "14") (pinfunction "~{H_INT}_14") (pintype "bidirectional"))
      (node (ref "U9") (pin "11") (pinfunction "26-IOD_11") (pintype "bidirectional"))
    )
    (net (code "34") (name "IMU-RST") (class "Default")
      (node (ref "TP5") (pin "P$1") (pinfunction "1_P$1") (pintype "bidirectional"))
      (node (ref "U4") (pin "11") (pinfunction "~{RST}_11") (pintype "bidirectional"))
      (node (ref "U9") (pin "12") (pinfunction "27-IO_12") (pintype "bidirectional"))
    )
    (net (code "35") (name "IO1-RST") (class "Default")
      (node (ref "TP3") (pin "P$1") (pinfunction "1_P$1") (pintype "bidirectional"))
      (node (ref "U5") (pin "23") (pinfunction "~{RESET}_23") (pintype "bidirectional"))
      (node (ref "U9") (pin "10") (pinfunction "25-IOD_10") (pintype "bidirectional"))
    )
    (net (code "36") (name "IO2-RST") (class "Default")
      (node (ref "TP16") (pin "P$1") (pinfunction "1_P$1") (pintype "bidirectional"))
      (node (ref "U6") (pin "23") (pinfunction "~{RESET}_23") (pintype "bidirectional"))
      (node (ref "U9") (pin "26") (pinfunction "4-IO_26") (pintype "bidirectional"))
    )
    (net (code "37") (name "Net-(B1-A_OUT1)") (class "Default")
      (node (ref "B1") (pin "2") (pinfunction "A_OUT1_2") (pintype "output"))
      (node (ref "J8") (pin "2") (pinfunction "1_2") (pintype "passive"))
    )
    (net (code "38") (name "Net-(B1-A_OUT2)") (class "Default")
      (node (ref "B1") (pin "4") (pinfunction "A_OUT2_4") (pintype "output"))
      (node (ref "J8") (pin "1") (pinfunction "2_1") (pintype "passive"))
    )
    (net (code "39") (name "Net-(B1-B_OUT1)") (class "Default")
      (node (ref "B1") (pin "7") (pinfunction "B_OUT1_7") (pintype "output"))
      (node (ref "J9") (pin "1") (pinfunction "2_1") (pintype "passive"))
    )
    (net (code "40") (name "Net-(B1-B_OUT2)") (class "Default")
      (node (ref "B1") (pin "5") (pinfunction "B_OUT2_5") (pintype "output"))
      (node (ref "J9") (pin "2") (pinfunction "1_2") (pintype "passive"))
    )
    (net (code "41") (name "Net-(B1-VCP)") (class "Default")
      (node (ref "B1") (pin "11") (pinfunction "VCP_11") (pintype "bidirectional"))
      (node (ref "C20") (pin "2") (pinfunction "2_2") (pintype "passive"))
    )
    (net (code "42") (name "Net-(B1-VINT)") (class "Default")
      (node (ref "B1") (pin "14") (pinfunction "VINT_14") (pintype "power_in"))
      (node (ref "C12") (pin "1") (pinfunction "1_1") (pintype "passive"))
    )
    (net (code "43") (name "Net-(B2-A_OUT1)") (class "Default")
      (node (ref "B2") (pin "2") (pinfunction "A_OUT1_2") (pintype "output"))
      (node (ref "J10") (pin "2") (pinfunction "1_2") (pintype "passive"))
    )
    (net (code "44") (name "Net-(B2-A_OUT2)") (class "Default")
      (node (ref "B2") (pin "4") (pinfunction "A_OUT2_4") (pintype "output"))
      (node (ref "J10") (pin "1") (pinfunction "2_1") (pintype "passive"))
    )
    (net (code "45") (name "Net-(B2-B_OUT1)") (class "Default")
      (node (ref "B2") (pin "7") (pinfunction "B_OUT1_7") (pintype "output"))
      (node (ref "J11") (pin "1") (pinfunction "2_1") (pintype "passive"))
    )
    (net (code "46") (name "Net-(B2-B_OUT2)") (class "Default")
      (node (ref "B2") (pin "5") (pinfunction "B_OUT2_5") (pintype "output"))
      (node (ref "J11") (pin "2") (pinfunction "1_2") (pintype "passive"))
    )
    (net (code "47") (name "Net-(B2-VCP)") (class "Default")
      (node (ref "B2") (pin "11") (pinfunction "VCP_11") (pintype "bidirectional"))
      (node (ref "C23") (pin "2") (pinfunction "2_2") (pintype "passive"))
    )
    (net (code "48") (name "Net-(B2-VINT)") (class "Default")
      (node (ref "B2") (pin "14") (pinfunction "VINT_14") (pintype "power_in"))
      (node (ref "C14") (pin "1") (pinfunction "1_1") (pintype "passive"))
    )
    (net (code "49") (name "Net-(B3-A_OUT1)") (class "Default")
      (node (ref "B3") (pin "2") (pinfunction "A_OUT1_2") (pintype "output"))
      (node (ref "J12") (pin "2") (pinfunction "1_2") (pintype "passive"))
    )
    (net (code "50") (name "Net-(B3-A_OUT2)") (class "Default")
      (node (ref "B3") (pin "4") (pinfunction "A_OUT2_4") (pintype "output"))
      (node (ref "J12") (pin "1") (pinfunction "2_1") (pintype "passive"))
    )
    (net (code "51") (name "Net-(B3-B_OUT1)") (class "Default")
      (node (ref "B3") (pin "7") (pinfunction "B_OUT1_7") (pintype "output"))
      (node (ref "J13") (pin "1") (pinfunction "2_1") (pintype "passive"))
    )
    (net (code "52") (name "Net-(B3-B_OUT2)") (class "Default")
      (node (ref "B3") (pin "5") (pinfunction "B_OUT2_5") (pintype "output"))
      (node (ref "J13") (pin "2") (pinfunction "1_2") (pintype "passive"))
    )
    (net (code "53") (name "Net-(B3-VCP)") (class "Default")
      (node (ref "B3") (pin "11") (pinfunction "VCP_11") (pintype "bidirectional"))
      (node (ref "C26") (pin "2") (pinfunction "2_2") (pintype "passive"))
    )
    (net (code "54") (name "Net-(B3-VINT)") (class "Default")
      (node (ref "B3") (pin "14") (pinfunction "VINT_14") (pintype "power_in"))
      (node (ref "C16") (pin "1") (pinfunction "1_1") (pintype "passive"))
    )
    (net (code "55") (name "Net-(B4-A_OUT1)") (class "Default")
      (node (ref "B4") (pin "2") (pinfunction "A_OUT1_2") (pintype "output"))
      (node (ref "J14") (pin "2") (pinfunction "1_2") (pintype "passive"))
    )
    (net (code "56") (name "Net-(B4-A_OUT2)") (class "Default")
      (node (ref "B4") (pin "4") (pinfunction "A_OUT2_4") (pintype "output"))
      (node (ref "J14") (pin "1") (pinfunction "2_1") (pintype "passive"))
    )
    (net (code "57") (name "Net-(B4-B_OUT1)") (class "Default")
      (node (ref "B4") (pin "7") (pinfunction "B_OUT1_7") (pintype "output"))
      (node (ref "J15") (pin "1") (pinfunction "2_1") (pintype "passive"))
    )
    (net (code "58") (name "Net-(B4-B_OUT2)") (class "Default")
      (node (ref "B4") (pin "5") (pinfunction "B_OUT2_5") (pintype "output"))
      (node (ref "J15") (pin "2") (pinfunction "1_2") (pintype "passive"))
    )
    (net (code "59") (name "Net-(B4-VCP)") (class "Default")
      (node (ref "B4") (pin "11") (pinfunction "VCP_11") (pintype "bidirectional"))
      (node (ref "C32") (pin "2") (pinfunction "2_2") (pintype "passive"))
    )
    (net (code "60") (name "Net-(B4-VINT)") (class "Default")
      (node (ref "B4") (pin "14") (pinfunction "VINT_14") (pintype "power_in"))
      (node (ref "C17") (pin "1") (pinfunction "1_1") (pintype "passive"))
    )
    (net (code "61") (name "Net-(D2-PadC)") (class "Default")
      (node (ref "D2") (pin "C") (pinfunction "C_C") (pintype "passive"))
      (node (ref "R2") (pin "1") (pinfunction "1_1") (pintype "passive"))
    )
    (net (code "62") (name "Net-(Q1-B)") (class "Default")
      (node (ref "Q1") (pin "1") (pinfunction "B_1") (pintype "passive"))
      (node (ref "R10") (pin "2") (pinfunction "2_2") (pintype "passive"))
    )
    (net (code "63") (name "Net-(Q2-B)") (class "Default")
      (node (ref "Q2") (pin "1") (pinfunction "B_1") (pintype "passive"))
      (node (ref "R9") (pin "2") (pinfunction "2_2") (pintype "passive"))
    )
    (net (code "64") (name "Net-(Q3-S)") (class "Default")
      (node (ref "C6") (pin "1") (pinfunction "1_1") (pintype "passive"))
      (node (ref "D1") (pin "C") (pinfunction "C_C") (pintype "passive"))
      (node (ref "Q3") (pin "2") (pinfunction "S_2") (pintype "passive"))
      (node (ref "S1") (pin "3") (pinfunction "S_3") (pintype "passive"))
      (node (ref "U2") (pin "1") (pinfunction "IN_1") (pintype "power_in"))
    )
    (net (code "65") (name "Net-(S1-P)") (class "Default")
      (node (ref "S1") (pin "2") (pinfunction "P_2") (pintype "passive"))
      (node (ref "U2") (pin "3") (pinfunction "EN_3") (pintype "input"))
    )
    (net (code "66") (name "Net-(TP6-1)") (class "Default")
      (node (ref "TP6") (pin "P$1") (pinfunction "1_P$1") (pintype "bidirectional"))
      (node (ref "U9") (pin "13") (pinfunction "14-IO_13") (pintype "bidirectional"))
    )
    (net (code "67") (name "Net-(TP7-1)") (class "Default")
      (node (ref "TP7") (pin "P$1") (pinfunction "1_P$1") (pintype "bidirectional"))
      (node (ref "U9") (pin "7") (pinfunction "35-IA_7") (pintype "bidirectional"))
    )
    (net (code "68") (name "Net-(TP8-1)") (class "Default")
      (node (ref "TP8") (pin "P$1") (pinfunction "1_P$1") (pintype "bidirectional"))
      (node (ref "U9") (pin "6") (pinfunction "34-IA_6") (pintype "bidirectional"))
    )
    (net (code "69") (name "Net-(TP9-1)") (class "Default")
      (node (ref "TP9") (pin "P$1") (pinfunction "1_P$1") (pintype "bidirectional"))
      (node (ref "U9") (pin "5") (pinfunction "39-I_5") (pintype "bidirectional"))
    )
    (net (code "70") (name "Net-(TP10-1)") (class "Default")
      (node (ref "TP10") (pin "P$1") (pinfunction "1_P$1") (pintype "bidirectional"))
      (node (ref "U9") (pin "4") (pinfunction "36-I_4") (pintype "bidirectional"))
    )
    (net (code "71") (name "Net-(U1-2)") (class "Default")
      (node (ref "R7") (pin "1") (pinfunction "1_1") (pintype "passive"))
      (node (ref "U1") (pin "BLUE") (pinfunction "2_BLUE") (pintype "passive"))
    )
    (net (code "72") (name "Net-(U1-3)") (class "Default")
      (node (ref "R6") (pin "1") (pinfunction "1_1") (pintype "passive"))
      (node (ref "U1") (pin "GREEN") (pinfunction "3_GREEN") (pintype "passive"))
    )
    (net (code "73") (name "Net-(U1-4)") (class "Default")
      (node (ref "R5") (pin "1") (pinfunction "1_1") (pintype "passive"))
      (node (ref "U1") (pin "RED") (pinfunction "4_RED") (pintype "passive"))
    )
    (net (code "74") (name "Net-(U3-PROG)") (class "Default")
      (node (ref "JP1") (pin "1") (pinfunction "1_1") (pintype "passive"))
      (node (ref "R4") (pin "2") (pinfunction "2_2") (pintype "passive"))
      (node (ref "U3") (pin "5") (pinfunction "PROG_5") (pintype "input"))
    )
    (net (code "75") (name "Net-(U3-STAT)") (class "Default")
      (node (ref "R2") (pin "2") (pinfunction "2_2") (pintype "passive"))
      (node (ref "U3") (pin "1") (pinfunction "STAT_1") (pintype "output"))
    )
    (net (code "76") (name "Net-(U4-CAP)") (class "Default")
      (node (ref "C1") (pin "1") (pinfunction "1_1") (pintype "passive"))
      (node (ref "U4") (pin "9") (pinfunction "CAP_9") (pintype "bidirectional"))
    )
    (net (code "77") (name "Net-(U4-S_SCL)") (class "Default")
      (node (ref "R15") (pin "1") (pinfunction "1_1") (pintype "passive"))
      (node (ref "U4") (pin "15") (pinfunction "S_SCL_15") (pintype "bidirectional"))
    )
    (net (code "78") (name "Net-(U4-S_SDA)") (class "Default")
      (node (ref "R8") (pin "1") (pinfunction "1_1") (pintype "passive"))
      (node (ref "U4") (pin "16") (pinfunction "S_SDA_16") (pintype "bidirectional"))
    )
    (net (code "79") (name "Net-(U7A-D+)") (class "Default")
      (node (ref "J1") (pin "D+") (pinfunction "D+_D+") (pintype "bidirectional"))
      (node (ref "U7") (pin "3") (pinfunction "D+_3") (pintype "bidirectional"))
    )
    (net (code "80") (name "Net-(U7A-D-)") (class "Default")
      (node (ref "J1") (pin "D-") (pinfunction "D-_D-") (pintype "bidirectional"))
      (node (ref "U7") (pin "4") (pinfunction "D-_4") (pintype "bidirectional"))
    )
    (net (code "81") (name "RED") (class "Default")
      (node (ref "R5") (pin "2") (pinfunction "2_2") (pintype "passive"))
      (node (ref "TP20") (pin "P$1") (pinfunction "1_P$1") (pintype "bidirectional"))
      (node (ref "U9") (pin "31") (pinfunction "19-IO_31") (pintype "bidirectional"))
    )
    (net (code "82") (name "RTS") (class "Default")
      (node (ref "Q1") (pin "2") (pinfunction "E_2") (pintype "passive"))
      (node (ref "R9") (pin "1") (pinfunction "1_1") (pintype "passive"))
      (node (ref "U7") (pin "19") (pinfunction "RTS_19") (pintype "output"))
    )
    (net (code "83") (name "RX") (class "Default")
      (node (ref "U7") (pin "21") (pinfunction "TXD_21") (pintype "output"))
      (node (ref "U9") (pin "34") (pinfunction "RX_34") (pintype "bidirectional"))
    )
    (net (code "84") (name "S1-SIG") (class "Default")
      (node (ref "J4") (pin "3") (pinfunction "3_3") (pintype "passive"))
      (node (ref "TP2") (pin "P$1") (pinfunction "1_P$1") (pintype "bidirectional"))
      (node (ref "U9") (pin "9") (pinfunction "33-IOA_9") (pintype "bidirectional"))
    )
    (net (code "85") (name "S2-SIG") (class "Default")
      (node (ref "J5") (pin "3") (pinfunction "3_3") (pintype "passive"))
      (node (ref "TP1") (pin "P$1") (pinfunction "1_P$1") (pintype "bidirectional"))
      (node (ref "U9") (pin "8") (pinfunction "32-IOA_8") (pintype "bidirectional"))
    )
    (net (code "86") (name "S3-SIG") (class "Default")
      (node (ref "J6") (pin "3") (pinfunction "3_3") (pintype "passive"))
      (node (ref "TP14") (pin "P$1") (pinfunction "1_P$1") (pintype "bidirectional"))
      (node (ref "U9") (pin "37") (pinfunction "23-IO_37") (pintype "bidirectional"))
    )
    (net (code "87") (name "S4-SIG") (class "Default")
      (node (ref "J7") (pin "3") (pinfunction "3_3") (pintype "passive"))
      (node (ref "TP15") (pin "P$1") (pinfunction "1_P$1") (pintype "bidirectional"))
      (node (ref "U9") (pin "27") (pinfunction "16-IO_27") (pintype "bidirectional"))
    )
    (net (code "88") (name "SCL") (class "Default")
      (node (ref "R14") (pin "2") (pinfunction "2_2") (pintype "passive"))
      (node (ref "TP18") (pin "P$1") (pinfunction "1_P$1") (pintype "bidirectional"))
      (node (ref "U10") (pin "P$7") (pinfunction "SCL_P$7") (pintype "output"))
      (node (ref "U4") (pin "19") (pinfunction "H_SCL/SCLK/RX_19") (pintype "bidirectional"))
      (node (ref "U5") (pin "25") (pinfunction "SCL_25") (pintype "bidirectional"))
      (node (ref "U6") (pin "25") (pinfunction "SCL_25") (pintype "bidirectional"))
      (node (ref "U9") (pin "36") (pinfunction "22-IO_36") (pintype "bidirectional"))
    )
    (net (code "89") (name "SDA") (class "Default")
      (node (ref "R13") (pin "1") (pinfunction "1_1") (pintype "passive"))
      (node (ref "TP19") (pin "P$1") (pinfunction "1_P$1") (pintype "bidirectional"))
      (node (ref "U10") (pin "P$8") (pinfunction "SDA_P$8") (pintype "input"))
      (node (ref "U4") (pin "20") (pinfunction "H_SDA/MISO/TX_20") (pintype "bidirectional"))
      (node (ref "U5") (pin "24") (pinfunction "SDA_24") (pintype "bidirectional"))
      (node (ref "U6") (pin "24") (pinfunction "SDA_24") (pintype "bidirectional"))
      (node (ref "U9") (pin "33") (pinfunction "21-IO_33") (pintype "bidirectional"))
    )
    (net (code "90") (name "TX") (class "Default")
      (node (ref "U7") (pin "20") (pinfunction "RXD_20") (pintype "input"))
      (node (ref "U9") (pin "35") (pinfunction "TX_35") (pintype "bidirectional"))
    )
    (net (code "91") (name "VBAT") (class "Default")
      (node (ref "B1") (pin "12") (pinfunction "VM_12") (pintype "power_in"))
      (node (ref "B2") (pin "12") (pinfunction "VM_12") (pintype "power_in"))
      (node (ref "B3") (pin "12") (pinfunction "VM_12") (pintype "power_in"))
      (node (ref "B4") (pin "12") (pinfunction "VM_12") (pintype "power_in"))
      (node (ref "C11") (pin "1") (pinfunction "1_1") (pintype "passive"))
      (node (ref "C19") (pin "1") (pinfunction "1_1") (pintype "passive"))
      (node (ref "C20") (pin "1") (pinfunction "1_1") (pintype "passive"))
      (node (ref "C22") (pin "1") (pinfunction "1_1") (pintype "passive"))
      (node (ref "C23") (pin "1") (pinfunction "1_1") (pintype "passive"))
      (node (ref "C25") (pin "1") (pinfunction "1_1") (pintype "passive"))
      (node (ref "C26") (pin "1") (pinfunction "1_1") (pintype "passive"))
      (node (ref "C28") (pin "+") (pinfunction "+_+") (pintype "passive"))
      (node (ref "C29") (pin "+") (pinfunction "+_+") (pintype "passive"))
      (node (ref "C3") (pin "1") (pinfunction "1_1") (pintype "passive"))
      (node (ref "C30") (pin "+") (pinfunction "+_+") (pintype "passive"))
      (node (ref "C31") (pin "+") (pinfunction "+_+") (pintype "passive"))
      (node (ref "C32") (pin "1") (pinfunction "1_1") (pintype "passive"))
      (node (ref "C5") (pin "1") (pinfunction "1_1") (pintype "passive"))
      (node (ref "J2") (pin "2") (pinfunction "1_2") (pintype "passive"))
      (node (ref "J4") (pin "1") (pinfunction "1_1") (pintype "passive"))
      (node (ref "J5") (pin "1") (pinfunction "1_1") (pintype "passive"))
      (node (ref "J6") (pin "1") (pinfunction "1_1") (pintype "passive"))
      (node (ref "J7") (pin "1") (pinfunction "1_1") (pintype "passive"))
      (node (ref "Q3") (pin "3") (pinfunction "D_3") (pintype "passive"))
      (node (ref "U10") (pin "P$2") (pinfunction "CELL_P$2") (pintype "input"))
      (node (ref "U10") (pin "P$3") (pinfunction "VDD_P$3") (pintype "bidirectional"))
      (node (ref "U3") (pin "3") (pinfunction "VBAT_3") (pintype "power_in"))
    )
    (net (code "92") (name "VUSB") (class "Default")
      (node (ref "C9") (pin "1") (pinfunction "1_1") (pintype "passive"))
      (node (ref "D1") (pin "A") (pinfunction "A_A") (pintype "passive"))
      (node (ref "D2") (pin "A") (pinfunction "A_A") (pintype "passive"))
      (node (ref "J1") (pin "VBUS") (pinfunction "VBUS_VBUS") (pintype "power_in"))
      (node (ref "JP1") (pin "2") (pinfunction "2_2") (pintype "passive"))
      (node (ref "Q3") (pin "1") (pinfunction "G_1") (pintype "passive"))
      (node (ref "R12") (pin "2") (pinfunction "2_2") (pintype "passive"))
      (node (ref "U3") (pin "4") (pinfunction "VDD_4") (pintype "power_in"))
      (node (ref "U7") (pin "8") (pinfunction "VBUS_8") (pintype "power_in"))
    )
    (net (code "93") (name "unconnected-(J1-PadID)") (class "Default")
      (node (ref "J1") (pin "ID") (pinfunction "ID_ID") (pintype "bidirectional"))
    )
    (net (code "94") (name "unconnected-(U2-P4-Pad4)") (class "Default")
      (node (ref "U2") (pin "4") (pinfunction "P4_4") (pintype "bidirectional"))
    )
    (net (code "95") (name "unconnected-(U4-XIN32-Pad27)") (class "Default")
      (node (ref "U4") (pin "27") (pinfunction "XIN32_27") (pintype "bidirectional"))
    )
    (net (code "96") (name "unconnected-(U4-~{H_CS}-Pad18)") (class "Default")
      (node (ref "U4") (pin "18") (pinfunction "~{H_CS}_18") (pintype "bidirectional"))
    )
    (net (code "97") (name "unconnected-(U5-I{slash}O[0]-Pad27)") (class "Default")
      (node (ref "U5") (pin "27") (pinfunction "I/O[0]_27") (pintype "bidirectional"))
    )
    (net (code "98") (name "unconnected-(U5-I{slash}O[7]-Pad8)") (class "Default")
      (node (ref "U5") (pin "8") (pinfunction "I/O[7]_8") (pintype "bidirectional"))
    )
    (net (code "99") (name "unconnected-(U5-I{slash}O[8]-Pad13)") (class "Default")
      (node (ref "U5") (pin "13") (pinfunction "I/O[8]_13") (pintype "bidirectional"))
    )
    (net (code "100") (name "unconnected-(U5-I{slash}O[15]-Pad22)") (class "Default")
      (node (ref "U5") (pin "22") (pinfunction "I/O[15]_22") (pintype "bidirectional"))
    )
    (net (code "101") (name "unconnected-(U5-OSCIO-Pad11)") (class "Default")
      (node (ref "U5") (pin "11") (pinfunction "OSCIO_11") (pintype "bidirectional"))
    )
    (net (code "102") (name "unconnected-(U5-~{INT}-Pad9)") (class "Default")
      (node (ref "U5") (pin "9") (pinfunction "~{INT}_9") (pintype "bidirectional"))
    )
    (net (code "103") (name "unconnected-(U6-I{slash}O[0]-Pad27)") (class "Default")
      (node (ref "U6") (pin "27") (pinfunction "I/O[0]_27") (pintype "bidirectional"))
    )
    (net (code "104") (name "unconnected-(U6-I{slash}O[7]-Pad8)") (class "Default")
      (node (ref "U6") (pin "8") (pinfunction "I/O[7]_8") (pintype "bidirectional"))
    )
    (net (code "105") (name "unconnected-(U6-I{slash}O[8]-Pad13)") (class "Default")
      (node (ref "U6") (pin "13") (pinfunction "I/O[8]_13") (pintype "bidirectional"))
    )
    (net (code "106") (name "unconnected-(U6-I{slash}O[15]-Pad22)") (class "Default")
      (node (ref "U6") (pin "22") (pinfunction "I/O[15]_22") (pintype "bidirectional"))
    )
    (net (code "107") (name "unconnected-(U6-OSCIO-Pad11)") (class "Default")
      (node (ref "U6") (pin "11") (pinfunction "OSCIO_11") (pintype "bidirectional"))
    )
    (net (code "108") (name "unconnected-(U6-~{INT}-Pad9)") (class "Default")
      (node (ref "U6") (pin "9") (pinfunction "~{INT}_9") (pintype "bidirectional"))
    )
    (net (code "109") (name "unconnected-(U7A-#RST-Pad9)") (class "Default")
      (node (ref "U7") (pin "9") (pinfunction "#RST_9") (pintype "bidirectional"))
    )
    (net (code "110") (name "unconnected-(U7A-#SUSPEND-Pad15)") (class "Default")
      (node (ref "U7") (pin "15") (pinfunction "#SUSPEND_15") (pintype "output"))
    )
    (net (code "111") (name "unconnected-(U7A-CTS-Pad18)") (class "Default")
      (node (ref "U7") (pin "18") (pinfunction "CTS_18") (pintype "input"))
    )
    (net (code "112") (name "unconnected-(U7A-DCD-Pad24)") (class "Default")
      (node (ref "U7") (pin "24") (pinfunction "DCD_24") (pintype "input"))
    )
    (net (code "113") (name "unconnected-(U7A-DSR-Pad22)") (class "Default")
      (node (ref "U7") (pin "22") (pinfunction "DSR_22") (pintype "input"))
    )
    (net (code "114") (name "unconnected-(U7A-GPIO0{slash}TXLED-Pad14)") (class "Default")
      (node (ref "U7") (pin "14") (pinfunction "GPIO0/TXLED_14") (pintype "bidirectional"))
    )
    (net (code "115") (name "unconnected-(U7A-GPIO1{slash}RXLED-Pad13)") (class "Default")
      (node (ref "U7") (pin "13") (pinfunction "GPIO1/RXLED_13") (pintype "bidirectional"))
    )
    (net (code "116") (name "unconnected-(U7A-GPIO2-Pad12)") (class "Default")
      (node (ref "U7") (pin "12") (pinfunction "GPIO2_12") (pintype "bidirectional"))
    )
    (net (code "117") (name "unconnected-(U7A-GPIO3-Pad11)") (class "Default")
      (node (ref "U7") (pin "11") (pinfunction "GPIO3_11") (pintype "bidirectional"))
    )
    (net (code "118") (name "unconnected-(U7A-NC-Pad10)") (class "Default")
      (node (ref "U7") (pin "10") (pinfunction "NC_10") (pintype "no_connect"))
    )
    (net (code "119") (name "unconnected-(U7A-RI-Pad1)") (class "Default")
      (node (ref "U7") (pin "1") (pinfunction "RI_1") (pintype "input"))
    )
    (net (code "120") (name "unconnected-(U7A-SUSPEND-Pad17)") (class "Default")
      (node (ref "U7") (pin "17") (pinfunction "SUSPEND_17") (pintype "output"))
    )
    (net (code "121") (name "unconnected-(U7A-VPP-Pad16)") (class "Default")
      (node (ref "U7") (pin "16") (pinfunction "VPP_16") (pintype "bidirectional"))
    )
    (net (code "122") (name "unconnected-(U9-2-Pad24)") (class "Default")
      (node (ref "U9") (pin "24") (pinfunction "2_24") (pintype "bidirectional"))
    )
    (net (code "123") (name "unconnected-(U9-5-Pad29)") (class "Default")
      (node (ref "U9") (pin "29") (pinfunction "5_29") (pintype "bidirectional"))
    )
    (net (code "124") (name "unconnected-(U9-12-Pad14)") (class "Default")
      (node (ref "U9") (pin "14") (pinfunction "12_14") (pintype "bidirectional"))
    )
    (net (code "125") (name "unconnected-(U9-15-Pad23)") (class "Default")
      (node (ref "U9") (pin "23") (pinfunction "15_23") (pintype "bidirectional"))
    )
    (net (code "126") (name "unconnected-(U9-NC-Pad32)") (class "Default")
      (node (ref "U9") (pin "32") (pinfunction "NC_32") (pintype "bidirectional"))
    )
    (net (code "127") (name "unconnected-(U9-SCK-Pad20)") (class "Default")
      (node (ref "U9") (pin "20") (pinfunction "SCK_20") (pintype "bidirectional"))
    )
    (net (code "128") (name "unconnected-(U9-SCS-Pad19)") (class "Default")
      (node (ref "U9") (pin "19") (pinfunction "SCS_19") (pintype "bidirectional"))
    )
    (net (code "129") (name "unconnected-(U9-SDI-Pad22)") (class "Default")
      (node (ref "U9") (pin "22") (pinfunction "SDI_22") (pintype "bidirectional"))
    )
    (net (code "130") (name "unconnected-(U9-SDO-Pad21)") (class "Default")
      (node (ref "U9") (pin "21") (pinfunction "SDO_21") (pintype "bidirectional"))
    )
    (net (code "131") (name "unconnected-(U9-SHD-Pad17)") (class "Default")
      (node (ref "U9") (pin "17") (pinfunction "SHD_17") (pintype "bidirectional"))
    )
    (net (code "132") (name "unconnected-(U9-SWP-Pad18)") (class "Default")
      (node (ref "U9") (pin "18") (pinfunction "SWP_18") (pintype "bidirectional"))
    )
    (net (code "133") (name "unconnected-(U10-~{ALRT}-PadP$5)") (class "Default")
      (node (ref "U10") (pin "P$5") (pinfunction "~{ALRT}_P$5") (pintype "bidirectional"))
    )
  )
)
